# Microcontroller.net
KiCad netlist of a schematic drawn in Altium Designer
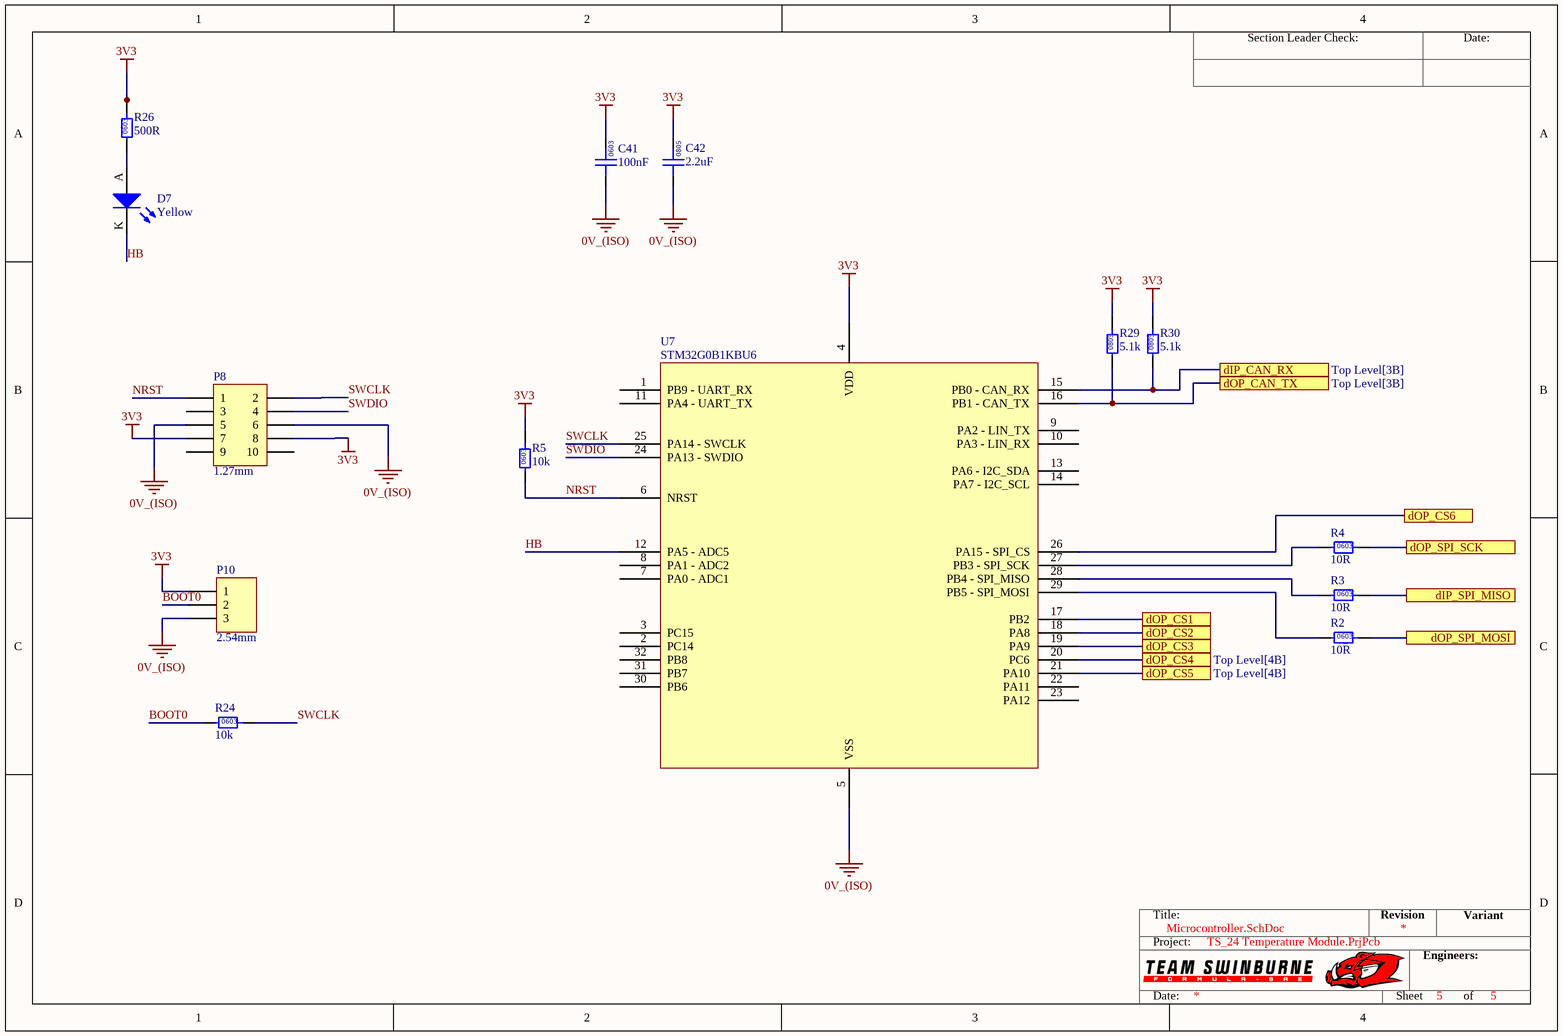
[diagram p0: Microcontroller.SchDoc]

(export (version "E")
  (design (tool "Eeschema 10.0.6"))
  (components
    (comp (ref "C41")
      (value "100nF")
      (footprint "0603 Capacitor")
      (fields (field (name "TOLERANCE") "10%") (field (name "PART NUMBER") "GCM188L81H104KA57D"))
      (libsource (lib "Team Swinburne") (part "100nF"))
    )
    (comp (ref "C42")
      (value "2.2uF")
      (footprint "GCM21BR71H105KA03L-Footprint-1")
      (fields (field (name "TOLERANCE") "10%") (field (name "PART NUMBER") "GRM21BR71E225KE11L"))
      (libsource (lib "Team Swinburne") (part "Component_1"))
    )
    (comp (ref "D7")
      (value "Yellow")
      (footprint "0805 LED")
      (description "Yellow LED Indication - Discrete 1.75V 0805 (2012 Metric)")
      (fields (field (name "PART NUMBER") "SML-211YTT86") (field (name "MANUFACTURER") "ROHM Semiconductor"))
      (libsource (lib "ts_standard_library") (part "LED"))
    )
    (comp (ref "P8")
      (value "1.27mm")
      (footprint "3221-10-0300-00")
      (fields
        (field (name "PART NUMBER") "SMD 1.27mm Header 2x5 (3221-10-0300-00)")
        (field (name "CONTACT") "NA")
      )
      (libsource (lib "ts_standard_connectors") (part "Header 2x5"))
    )
    (comp (ref "P10")
      (value "2.54mm")
      (footprint "TH 2.54mm Header 1x3")
      (fields (field (name "PART NUMBER") "TH 2.54mm Header 1x3") (field (name "CONTACT") "NA"))
      (libsource (lib "ts_standard_connectors") (part "Header 1x3"))
    )
    (comp (ref "R2")
      (value "10R")
      (footprint "0603")
      (fields
        (field (name "PART NUMBER") "RC0603FR-0710RL")
        (field (name "MANUFACTURER") "YAGEO")
        (field (name "TOLERANCE") "0.01")
      )
      (libsource (lib "ts_standard_library") (part "Resistor 0603"))
    )
    (comp (ref "R3")
      (value "10R")
      (footprint "0603")
      (fields
        (field (name "PART NUMBER") "RC0603FR-0710RL")
        (field (name "MANUFACTURER") "YAGEO")
        (field (name "TOLERANCE") "0.01")
      )
      (libsource (lib "ts_standard_library") (part "Resistor 0603"))
    )
    (comp (ref "R4")
      (value "10R")
      (footprint "0603")
      (fields
        (field (name "PART NUMBER") "RC0603FR-0710RL")
        (field (name "MANUFACTURER") "YAGEO")
        (field (name "TOLERANCE") "0.01")
      )
      (libsource (lib "ts_standard_library") (part "Resistor 0603"))
    )
    (comp (ref "R5")
      (value "10k")
      (footprint "0603")
      (fields
        (field (name "PART NUMBER") "RC0603FR-0710KL")
        (field (name "MANUFACTURER") "YAGEO")
        (field (name "TOLERANCE") "0.01")
      )
      (libsource (lib "ts_standard_library") (part "Resistor 0603"))
    )
    (comp (ref "R24")
      (value "10k")
      (footprint "0603")
      (fields
        (field (name "PART NUMBER") "RC0603FR-0710KL")
        (field (name "MANUFACTURER") "YAGEO")
        (field (name "TOLERANCE") "0.01")
      )
      (libsource (lib "ts_standard_library") (part "Resistor 0603"))
    )
    (comp (ref "R26")
      (value "500R")
      (footprint "0603")
      (fields
        (field (name "PART NUMBER") "RT0603BRD07500RL")
        (field (name "MANUFACTURER") "YAGEO")
        (field (name "TOLERANCE") "0.01")
      )
      (libsource (lib "ts_standard_library") (part "Resistor 0603"))
    )
    (comp (ref "R29")
      (value "5.1k")
      (footprint "0805")
      (fields
        (field (name "PART NUMBER") "RC0805FR075K1L")
        (field (name "MANUFACTURER") "YAGEO")
        (field (name "TOLERANCE") "0.01")
      )
      (libsource (lib "ts_standard_library") (part "Resistor 0805"))
    )
    (comp (ref "R30")
      (value "5.1k")
      (footprint "0805")
      (fields
        (field (name "PART NUMBER") "RC0805FR075K1L")
        (field (name "MANUFACTURER") "YAGEO")
        (field (name "TOLERANCE") "0.01")
      )
      (libsource (lib "ts_standard_library") (part "Resistor 0805"))
    )
    (comp (ref "U7")
      (value "STM32G0B1KBU6")
      (footprint "ST-UFQFPN32")
      (description "RISC Microcontroller, 32-Bit, FLASH, Cortex-M0+ CPU, 64MHz, CMOS")
      (libsource (lib "Team Swinburne") (part "STM32G0B1KBU6"))
    )
  )
  (nets
    (net (code "1") (name "/BOOT0") (class "Default")
      (node (ref "P10") (pin "2") (pinfunction "2_2") (pintype "passive"))
      (node (ref "R24") (pin "1") (pinfunction "1_1") (pintype "passive"))
    )
    (net (code "2") (name "/HB") (class "Default")
      (node (ref "D7") (pin "K") (pinfunction "K_K") (pintype "passive"))
      (node (ref "U7") (pin "12") (pinfunction "PA5_-_ADC5_12") (pintype "passive"))
    )
    (net (code "3") (name "/NRST") (class "Default")
      (node (ref "P8") (pin "1") (pinfunction "1_1") (pintype "passive"))
      (node (ref "R5") (pin "1") (pinfunction "1_1") (pintype "passive"))
      (node (ref "U7") (pin "6") (pinfunction "NRST_6") (pintype "passive"))
    )
    (net (code "4") (name "/SWCLK") (class "Default")
      (node (ref "P8") (pin "2") (pinfunction "2_2") (pintype "passive"))
      (node (ref "R24") (pin "2") (pinfunction "2_2") (pintype "passive"))
      (node (ref "U7") (pin "25") (pinfunction "PA14_-_SWCLK_25") (pintype "passive"))
    )
    (net (code "5") (name "/SWDIO") (class "Default")
      (node (ref "P8") (pin "4") (pinfunction "4_4") (pintype "passive"))
      (node (ref "U7") (pin "24") (pinfunction "PA13_-_SWDIO_24") (pintype "passive"))
    )
    (net (code "6") (name "/dIP_CAN_RX") (class "Default")
      (node (ref "R30") (pin "1") (pinfunction "1_1") (pintype "passive"))
      (node (ref "U7") (pin "15") (pinfunction "PB0_-_CAN_RX_15") (pintype "passive"))
    )
    (net (code "7") (name "/dIP_SPI_MISO") (class "Default")
      (node (ref "R3") (pin "2") (pinfunction "2_2") (pintype "passive"))
    )
    (net (code "8") (name "/dOP_CAN_TX") (class "Default")
      (node (ref "R29") (pin "1") (pinfunction "1_1") (pintype "passive"))
      (node (ref "U7") (pin "16") (pinfunction "PB1_-_CAN_TX_16") (pintype "passive"))
    )
    (net (code "9") (name "/dOP_CS1") (class "Default")
      (node (ref "U7") (pin "17") (pinfunction "PB2_17") (pintype "passive"))
    )
    (net (code "10") (name "/dOP_CS2") (class "Default")
      (node (ref "U7") (pin "18") (pinfunction "PA8_18") (pintype "passive"))
    )
    (net (code "11") (name "/dOP_CS3") (class "Default")
      (node (ref "U7") (pin "19") (pinfunction "PA9_19") (pintype "passive"))
    )
    (net (code "12") (name "/dOP_CS4") (class "Default")
      (node (ref "U7") (pin "20") (pinfunction "PC6_20") (pintype "passive"))
    )
    (net (code "13") (name "/dOP_CS5") (class "Default")
      (node (ref "U7") (pin "21") (pinfunction "PA10_21") (pintype "passive"))
    )
    (net (code "14") (name "/dOP_CS6") (class "Default")
      (node (ref "U7") (pin "26") (pinfunction "PA15_-_SPI_CS_26") (pintype "passive"))
    )
    (net (code "15") (name "/dOP_SPI_MOSI") (class "Default")
      (node (ref "R2") (pin "2") (pinfunction "2_2") (pintype "passive"))
    )
    (net (code "16") (name "/dOP_SPI_SCK") (class "Default")
      (node (ref "R4") (pin "2") (pinfunction "2_2") (pintype "passive"))
    )
    (net (code "17") (name "0V_(ISO)") (class "Default")
      (node (ref "C41") (pin "1") (pinfunction "1_1") (pintype "passive"))
      (node (ref "C42") (pin "1") (pinfunction "1_1") (pintype "passive"))
      (node (ref "P10") (pin "3") (pinfunction "3_3") (pintype "passive"))
      (node (ref "P8") (pin "5") (pinfunction "5_5") (pintype "passive"))
      (node (ref "P8") (pin "6") (pinfunction "6_6") (pintype "passive"))
      (node (ref "U7") (pin "5") (pinfunction "VSS_5") (pintype "passive"))
    )
    (net (code "18") (name "3V3") (class "Default")
      (node (ref "C41") (pin "2") (pinfunction "2_2") (pintype "passive"))
      (node (ref "C42") (pin "2") (pinfunction "2_2") (pintype "passive"))
      (node (ref "P10") (pin "1") (pinfunction "1_1") (pintype "passive"))
      (node (ref "P8") (pin "7") (pinfunction "7_7") (pintype "passive"))
      (node (ref "P8") (pin "8") (pinfunction "8_8") (pintype "passive"))
      (node (ref "R26") (pin "2") (pinfunction "2_2") (pintype "passive"))
      (node (ref "R29") (pin "2") (pinfunction "2_2") (pintype "passive"))
      (node (ref "R30") (pin "2") (pinfunction "2_2") (pintype "passive"))
      (node (ref "R5") (pin "2") (pinfunction "2_2") (pintype "passive"))
      (node (ref "U7") (pin "4") (pinfunction "VDD_4") (pintype "passive"))
    )
    (net (code "19") (name "Net-(D7-PadA)") (class "Default")
      (node (ref "D7") (pin "A") (pinfunction "A_A") (pintype "passive"))
      (node (ref "R26") (pin "1") (pinfunction "1_1") (pintype "passive"))
    )
    (net (code "20") (name "Net-(U7-PB3_-_SPI_SCK)") (class "Default")
      (node (ref "R4") (pin "1") (pinfunction "1_1") (pintype "passive"))
      (node (ref "U7") (pin "27") (pinfunction "PB3_-_SPI_SCK_27") (pintype "passive"))
    )
    (net (code "21") (name "Net-(U7-PB4_-_SPI_MISO)") (class "Default")
      (node (ref "R3") (pin "1") (pinfunction "1_1") (pintype "passive"))
      (node (ref "U7") (pin "28") (pinfunction "PB4_-_SPI_MISO_28") (pintype "passive"))
    )
    (net (code "22") (name "Net-(U7-PB5_-_SPI_MOSI)") (class "Default")
      (node (ref "R2") (pin "1") (pinfunction "1_1") (pintype "passive"))
      (node (ref "U7") (pin "29") (pinfunction "PB5_-_SPI_MOSI_29") (pintype "passive"))
    )
    (net (code "23") (name "unconnected-(P8-Pad3)") (class "Default")
      (node (ref "P8") (pin "3") (pinfunction "3_3") (pintype "passive"))
    )
    (net (code "24") (name "unconnected-(P8-Pad9)") (class "Default")
      (node (ref "P8") (pin "9") (pinfunction "9_9") (pintype "passive"))
    )
    (net (code "25") (name "unconnected-(P8-Pad10)") (class "Default")
      (node (ref "P8") (pin "10") (pinfunction "10_10") (pintype "passive"))
    )
    (net (code "26") (name "unconnected-(U7-PA0_-_ADC1-Pad7)") (class "Default")
      (node (ref "U7") (pin "7") (pinfunction "PA0_-_ADC1_7") (pintype "passive"))
    )
    (net (code "27") (name "unconnected-(U7-PA1_-_ADC2-Pad8)") (class "Default")
      (node (ref "U7") (pin "8") (pinfunction "PA1_-_ADC2_8") (pintype "passive"))
    )
    (net (code "28") (name "unconnected-(U7-PA2_-_LIN_TX-Pad9)") (class "Default")
      (node (ref "U7") (pin "9") (pinfunction "PA2_-_LIN_TX_9") (pintype "passive"))
    )
    (net (code "29") (name "unconnected-(U7-PA3_-_LIN_RX-Pad10)") (class "Default")
      (node (ref "U7") (pin "10") (pinfunction "PA3_-_LIN_RX_10") (pintype "passive"))
    )
    (net (code "30") (name "unconnected-(U7-PA4_-_UART_TX-Pad11)") (class "Default")
      (node (ref "U7") (pin "11") (pinfunction "PA4_-_UART_TX_11") (pintype "passive"))
    )
    (net (code "31") (name "unconnected-(U7-PA6_-_I2C_SDA-Pad13)") (class "Default")
      (node (ref "U7") (pin "13") (pinfunction "PA6_-_I2C_SDA_13") (pintype "passive"))
    )
    (net (code "32") (name "unconnected-(U7-PA7_-_I2C_SCL-Pad14)") (class "Default")
      (node (ref "U7") (pin "14") (pinfunction "PA7_-_I2C_SCL_14") (pintype "passive"))
    )
    (net (code "33") (name "unconnected-(U7-PA11-Pad22)") (class "Default")
      (node (ref "U7") (pin "22") (pinfunction "PA11_22") (pintype "passive"))
    )
    (net (code "34") (name "unconnected-(U7-PA12-Pad23)") (class "Default")
      (node (ref "U7") (pin "23") (pinfunction "PA12_23") (pintype "passive"))
    )
    (net (code "35") (name "unconnected-(U7-PB6-Pad30)") (class "Default")
      (node (ref "U7") (pin "30") (pinfunction "PB6_30") (pintype "passive"))
    )
    (net (code "36") (name "unconnected-(U7-PB7-Pad31)") (class "Default")
      (node (ref "U7") (pin "31") (pinfunction "PB7_31") (pintype "passive"))
    )
    (net (code "37") (name "unconnected-(U7-PB8-Pad32)") (class "Default")
      (node (ref "U7") (pin "32") (pinfunction "PB8_32") (pintype "passive"))
    )
    (net (code "38") (name "unconnected-(U7-PB9_-_UART_RX-Pad1)") (class "Default")
      (node (ref "U7") (pin "1") (pinfunction "PB9_-_UART_RX_1") (pintype "passive"))
    )
    (net (code "39") (name "unconnected-(U7-PC14-Pad2)") (class "Default")
      (node (ref "U7") (pin "2") (pinfunction "PC14_2") (pintype "passive"))
    )
    (net (code "40") (name "unconnected-(U7-PC15-Pad3)") (class "Default")
      (node (ref "U7") (pin "3") (pinfunction "PC15_3") (pintype "passive"))
    )
  )
)
